# buzzer.net
KiCad netlist of a schematic drawn in EAGLE
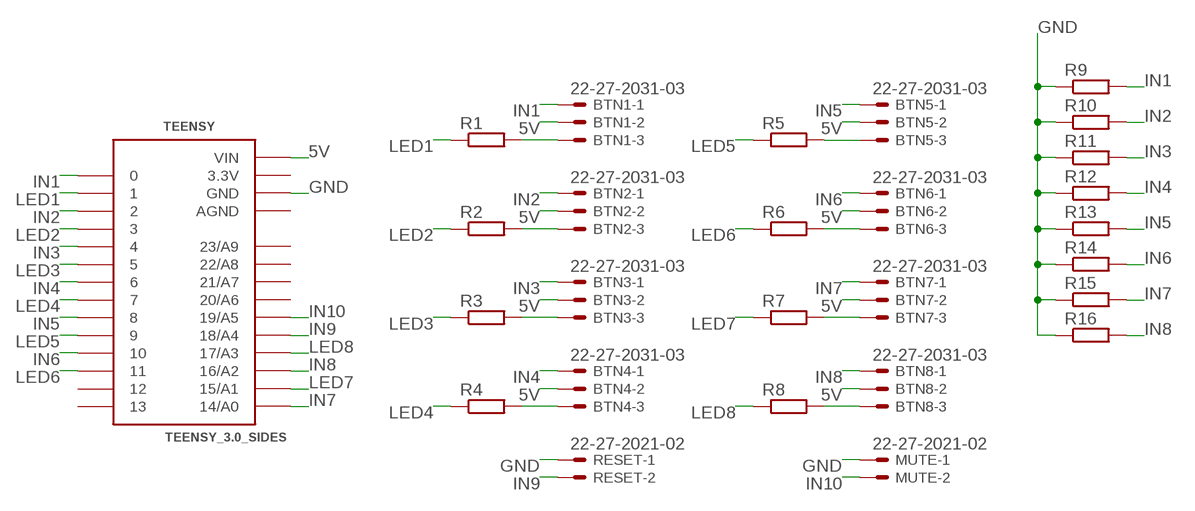
[diagram p0: schematic, sheet 1]

(export (version "E")
  (design (tool "Eeschema 10.0.6"))
  (components
    (comp (ref "BTN1")
      (value "22-27-2031-03")
      (footprint "eagle-import:6410-03")
      (libsource (lib "eagle-import") (part "22-?-0327-2031"))
    )
    (comp (ref "BTN2")
      (value "22-27-2031-03")
      (footprint "eagle-import:6410-03")
      (libsource (lib "eagle-import") (part "22-?-0327-2031"))
    )
    (comp (ref "BTN3")
      (value "22-27-2031-03")
      (footprint "eagle-import:6410-03")
      (libsource (lib "eagle-import") (part "22-?-0327-2031"))
    )
    (comp (ref "BTN4")
      (value "22-27-2031-03")
      (footprint "eagle-import:6410-03")
      (libsource (lib "eagle-import") (part "22-?-0327-2031"))
    )
    (comp (ref "BTN5")
      (value "22-27-2031-03")
      (footprint "eagle-import:6410-03")
      (libsource (lib "eagle-import") (part "22-?-0327-2031"))
    )
    (comp (ref "BTN6")
      (value "22-27-2031-03")
      (footprint "eagle-import:6410-03")
      (libsource (lib "eagle-import") (part "22-?-0327-2031"))
    )
    (comp (ref "BTN7")
      (value "22-27-2031-03")
      (footprint "eagle-import:6410-03")
      (libsource (lib "eagle-import") (part "22-?-0327-2031"))
    )
    (comp (ref "BTN8")
      (value "22-27-2031-03")
      (footprint "eagle-import:6410-03")
      (libsource (lib "eagle-import") (part "22-?-0327-2031"))
    )
    (comp (ref "MUTE")
      (value "22-27-2021-02")
      (footprint "eagle-import:6410-02")
      (libsource (lib "eagle-import") (part "22-?-0227-2021"))
    )
    (comp (ref "R1")
      (value "R0207/10")
      (footprint "eagle-import:0207_10")
      (libsource (lib "eagle-import") (part "R0207/10"))
    )
    (comp (ref "R2")
      (value "R0207/10")
      (footprint "eagle-import:0207_10")
      (libsource (lib "eagle-import") (part "R0207/10"))
    )
    (comp (ref "R3")
      (value "R0207/10")
      (footprint "eagle-import:0207_10")
      (libsource (lib "eagle-import") (part "R0207/10"))
    )
    (comp (ref "R4")
      (value "R0207/10")
      (footprint "eagle-import:0207_10")
      (libsource (lib "eagle-import") (part "R0207/10"))
    )
    (comp (ref "R5")
      (value "R0207/10")
      (footprint "eagle-import:0207_10")
      (libsource (lib "eagle-import") (part "R0207/10"))
    )
    (comp (ref "R6")
      (value "R0207/10")
      (footprint "eagle-import:0207_10")
      (libsource (lib "eagle-import") (part "R0207/10"))
    )
    (comp (ref "R7")
      (value "R0207/10")
      (footprint "eagle-import:0207_10")
      (libsource (lib "eagle-import") (part "R0207/10"))
    )
    (comp (ref "R8")
      (value "R0207/10")
      (footprint "eagle-import:0207_10")
      (libsource (lib "eagle-import") (part "R0207/10"))
    )
    (comp (ref "R9")
      (value "R0207/10")
      (footprint "eagle-import:0207_10")
      (libsource (lib "eagle-import") (part "R0207/10"))
    )
    (comp (ref "R10")
      (value "R0207/10")
      (footprint "eagle-import:0207_10")
      (libsource (lib "eagle-import") (part "R0207/10"))
    )
    (comp (ref "R11")
      (value "R0207/10")
      (footprint "eagle-import:0207_10")
      (libsource (lib "eagle-import") (part "R0207/10"))
    )
    (comp (ref "R12")
      (value "R0207/10")
      (footprint "eagle-import:0207_10")
      (libsource (lib "eagle-import") (part "R0207/10"))
    )
    (comp (ref "R13")
      (value "R0207/10")
      (footprint "eagle-import:0207_10")
      (libsource (lib "eagle-import") (part "R0207/10"))
    )
    (comp (ref "R14")
      (value "R0207/10")
      (footprint "eagle-import:0207_10")
      (libsource (lib "eagle-import") (part "R0207/10"))
    )
    (comp (ref "R15")
      (value "R0207/10")
      (footprint "eagle-import:0207_10")
      (libsource (lib "eagle-import") (part "R0207/10"))
    )
    (comp (ref "R16")
      (value "R0207/10")
      (footprint "eagle-import:0207_10")
      (libsource (lib "eagle-import") (part "R0207/10"))
    )
    (comp (ref "RESET")
      (value "22-27-2021-02")
      (footprint "eagle-import:6410-02")
      (libsource (lib "eagle-import") (part "22-?-0227-2021"))
    )
    (comp (ref "TEENSY")
      (value "TEENSY_3.0_SIDES")
      (footprint "eagle-import:TEENSY_3.0_SIDES")
      (libsource (lib "eagle-import") (part "TEENSY_3.0_SIDES"))
    )
  )
  (nets
    (net (code "1") (name "/3.3V") (class "Default")
      (node (ref "TEENSY") (pin "3.3V") (pinfunction "3.3V_3.3V") (pintype "power_in"))
    )
    (net (code "2") (name "/5V") (class "Default")
      (node (ref "BTN1") (pin "2") (pinfunction "S_2") (pintype "passive"))
      (node (ref "BTN2") (pin "2") (pinfunction "S_2") (pintype "passive"))
      (node (ref "BTN3") (pin "2") (pinfunction "S_2") (pintype "passive"))
      (node (ref "BTN4") (pin "2") (pinfunction "S_2") (pintype "passive"))
      (node (ref "BTN5") (pin "2") (pinfunction "S_2") (pintype "passive"))
      (node (ref "BTN6") (pin "2") (pinfunction "S_2") (pintype "passive"))
      (node (ref "BTN7") (pin "2") (pinfunction "S_2") (pintype "passive"))
      (node (ref "BTN8") (pin "2") (pinfunction "S_2") (pintype "passive"))
      (node (ref "TEENSY") (pin "VIN") (pinfunction "VIN_VIN") (pintype "power_in"))
    )
    (net (code "3") (name "/AGND") (class "Default")
      (node (ref "TEENSY") (pin "AGND") (pinfunction "AGND_AGND") (pintype "power_in"))
    )
    (net (code "4") (name "/GND") (class "Default")
      (node (ref "MUTE") (pin "1") (pinfunction "S_1") (pintype "passive"))
      (node (ref "R10") (pin "1") (pinfunction "1_1") (pintype "passive"))
      (node (ref "R11") (pin "1") (pinfunction "1_1") (pintype "passive"))
      (node (ref "R12") (pin "1") (pinfunction "1_1") (pintype "passive"))
      (node (ref "R13") (pin "1") (pinfunction "1_1") (pintype "passive"))
      (node (ref "R14") (pin "1") (pinfunction "1_1") (pintype "passive"))
      (node (ref "R15") (pin "1") (pinfunction "1_1") (pintype "passive"))
      (node (ref "R16") (pin "1") (pinfunction "1_1") (pintype "passive"))
      (node (ref "R9") (pin "1") (pinfunction "1_1") (pintype "passive"))
      (node (ref "RESET") (pin "1") (pinfunction "S_1") (pintype "passive"))
      (node (ref "TEENSY") (pin "GND") (pinfunction "GND_GND") (pintype "power_in"))
    )
    (net (code "5") (name "/IN1") (class "Default")
      (node (ref "BTN1") (pin "1") (pinfunction "S_1") (pintype "passive"))
      (node (ref "R9") (pin "2") (pinfunction "2_2") (pintype "passive"))
      (node (ref "TEENSY") (pin "0") (pinfunction "0_0") (pintype "bidirectional"))
    )
    (net (code "6") (name "/IN2") (class "Default")
      (node (ref "BTN2") (pin "1") (pinfunction "S_1") (pintype "passive"))
      (node (ref "R10") (pin "2") (pinfunction "2_2") (pintype "passive"))
      (node (ref "TEENSY") (pin "2") (pinfunction "2_2") (pintype "bidirectional"))
    )
    (net (code "7") (name "/IN3") (class "Default")
      (node (ref "BTN3") (pin "1") (pinfunction "S_1") (pintype "passive"))
      (node (ref "R11") (pin "2") (pinfunction "2_2") (pintype "passive"))
      (node (ref "TEENSY") (pin "4") (pinfunction "4_4") (pintype "bidirectional"))
    )
    (net (code "8") (name "/IN4") (class "Default")
      (node (ref "BTN4") (pin "1") (pinfunction "S_1") (pintype "passive"))
      (node (ref "R12") (pin "2") (pinfunction "2_2") (pintype "passive"))
      (node (ref "TEENSY") (pin "6") (pinfunction "6_6") (pintype "bidirectional"))
    )
    (net (code "9") (name "/IN5") (class "Default")
      (node (ref "BTN5") (pin "1") (pinfunction "S_1") (pintype "passive"))
      (node (ref "R13") (pin "2") (pinfunction "2_2") (pintype "passive"))
      (node (ref "TEENSY") (pin "8") (pinfunction "8_8") (pintype "bidirectional"))
    )
    (net (code "10") (name "/IN6") (class "Default")
      (node (ref "BTN6") (pin "1") (pinfunction "S_1") (pintype "passive"))
      (node (ref "R14") (pin "2") (pinfunction "2_2") (pintype "passive"))
      (node (ref "TEENSY") (pin "10") (pinfunction "10_10") (pintype "bidirectional"))
    )
    (net (code "11") (name "/IN7") (class "Default")
      (node (ref "BTN7") (pin "1") (pinfunction "S_1") (pintype "passive"))
      (node (ref "R15") (pin "2") (pinfunction "2_2") (pintype "passive"))
      (node (ref "TEENSY") (pin "14/A0") (pinfunction "14/A0_14/A0") (pintype "bidirectional"))
    )
    (net (code "12") (name "/IN8") (class "Default")
      (node (ref "BTN8") (pin "1") (pinfunction "S_1") (pintype "passive"))
      (node (ref "R16") (pin "2") (pinfunction "2_2") (pintype "passive"))
      (node (ref "TEENSY") (pin "16/A2") (pinfunction "16/A2_16/A2") (pintype "bidirectional"))
    )
    (net (code "13") (name "/IN9") (class "Default")
      (node (ref "RESET") (pin "2") (pinfunction "S_2") (pintype "passive"))
      (node (ref "TEENSY") (pin "18/A4") (pinfunction "18/A4_18/A4") (pintype "bidirectional"))
    )
    (net (code "14") (name "/IN10") (class "Default")
      (node (ref "MUTE") (pin "2") (pinfunction "S_2") (pintype "passive"))
      (node (ref "TEENSY") (pin "19/A5") (pinfunction "19/A5_19/A5") (pintype "bidirectional"))
    )
    (net (code "15") (name "/LED1") (class "Default")
      (node (ref "R1") (pin "1") (pinfunction "1_1") (pintype "passive"))
      (node (ref "TEENSY") (pin "1") (pinfunction "1_1") (pintype "bidirectional"))
    )
    (net (code "16") (name "/LED2") (class "Default")
      (node (ref "R2") (pin "1") (pinfunction "1_1") (pintype "passive"))
      (node (ref "TEENSY") (pin "3") (pinfunction "3_3") (pintype "bidirectional"))
    )
    (net (code "17") (name "/LED3") (class "Default")
      (node (ref "R3") (pin "1") (pinfunction "1_1") (pintype "passive"))
      (node (ref "TEENSY") (pin "5") (pinfunction "5_5") (pintype "bidirectional"))
    )
    (net (code "18") (name "/LED4") (class "Default")
      (node (ref "R4") (pin "1") (pinfunction "1_1") (pintype "passive"))
      (node (ref "TEENSY") (pin "7") (pinfunction "7_7") (pintype "bidirectional"))
    )
    (net (code "19") (name "/LED5") (class "Default")
      (node (ref "R5") (pin "1") (pinfunction "1_1") (pintype "passive"))
      (node (ref "TEENSY") (pin "9") (pinfunction "9_9") (pintype "bidirectional"))
    )
    (net (code "20") (name "/LED6") (class "Default")
      (node (ref "R6") (pin "1") (pinfunction "1_1") (pintype "passive"))
      (node (ref "TEENSY") (pin "11") (pinfunction "11_11") (pintype "bidirectional"))
    )
    (net (code "21") (name "/LED7") (class "Default")
      (node (ref "R7") (pin "1") (pinfunction "1_1") (pintype "passive"))
      (node (ref "TEENSY") (pin "15/A1") (pinfunction "15/A1_15/A1") (pintype "bidirectional"))
    )
    (net (code "22") (name "/LED8") (class "Default")
      (node (ref "R8") (pin "1") (pinfunction "1_1") (pintype "passive"))
      (node (ref "TEENSY") (pin "17/A3") (pinfunction "17/A3_17/A3") (pintype "bidirectional"))
    )
    (net (code "23") (name "Net-(BTN1C-S)") (class "Default")
      (node (ref "BTN1") (pin "3") (pinfunction "S_3") (pintype "passive"))
      (node (ref "R1") (pin "2") (pinfunction "2_2") (pintype "passive"))
    )
    (net (code "24") (name "Net-(BTN2C-S)") (class "Default")
      (node (ref "BTN2") (pin "3") (pinfunction "S_3") (pintype "passive"))
      (node (ref "R2") (pin "2") (pinfunction "2_2") (pintype "passive"))
    )
    (net (code "25") (name "Net-(BTN3C-S)") (class "Default")
      (node (ref "BTN3") (pin "3") (pinfunction "S_3") (pintype "passive"))
      (node (ref "R3") (pin "2") (pinfunction "2_2") (pintype "passive"))
    )
    (net (code "26") (name "Net-(BTN4C-S)") (class "Default")
      (node (ref "BTN4") (pin "3") (pinfunction "S_3") (pintype "passive"))
      (node (ref "R4") (pin "2") (pinfunction "2_2") (pintype "passive"))
    )
    (net (code "27") (name "Net-(BTN5C-S)") (class "Default")
      (node (ref "BTN5") (pin "3") (pinfunction "S_3") (pintype "passive"))
      (node (ref "R5") (pin "2") (pinfunction "2_2") (pintype "passive"))
    )
    (net (code "28") (name "Net-(BTN6C-S)") (class "Default")
      (node (ref "BTN6") (pin "3") (pinfunction "S_3") (pintype "passive"))
      (node (ref "R6") (pin "2") (pinfunction "2_2") (pintype "passive"))
    )
    (net (code "29") (name "Net-(BTN7C-S)") (class "Default")
      (node (ref "BTN7") (pin "3") (pinfunction "S_3") (pintype "passive"))
      (node (ref "R7") (pin "2") (pinfunction "2_2") (pintype "passive"))
    )
    (net (code "30") (name "Net-(BTN8C-S)") (class "Default")
      (node (ref "BTN8") (pin "3") (pinfunction "S_3") (pintype "passive"))
      (node (ref "R8") (pin "2") (pinfunction "2_2") (pintype "passive"))
    )
    (net (code "31") (name "unconnected-(TEENSY-Pad12)") (class "Default")
      (node (ref "TEENSY") (pin "12") (pinfunction "12_12") (pintype "bidirectional"))
    )
    (net (code "32") (name "unconnected-(TEENSY-Pad13)") (class "Default")
      (node (ref "TEENSY") (pin "13") (pinfunction "13_13") (pintype "bidirectional"))
    )
    (net (code "33") (name "unconnected-(TEENSY-Pad20{slash}A6)") (class "Default")
      (node (ref "TEENSY") (pin "20/A6") (pinfunction "20/A6_20/A6") (pintype "bidirectional"))
    )
    (net (code "34") (name "unconnected-(TEENSY-Pad21{slash}A7)") (class "Default")
      (node (ref "TEENSY") (pin "21/A7") (pinfunction "21/A7_21/A7") (pintype "bidirectional"))
    )
    (net (code "35") (name "unconnected-(TEENSY-Pad22{slash}A8)") (class "Default")
      (node (ref "TEENSY") (pin "22/A8") (pinfunction "22/A8_22/A8") (pintype "bidirectional"))
    )
    (net (code "36") (name "unconnected-(TEENSY-Pad23{slash}A9)") (class "Default")
      (node (ref "TEENSY") (pin "23/A9") (pinfunction "23/A9_23/A9") (pintype "bidirectional"))
    )
  )
)
